# final_1.net
KiCad netlist of a schematic drawn in EAGLE
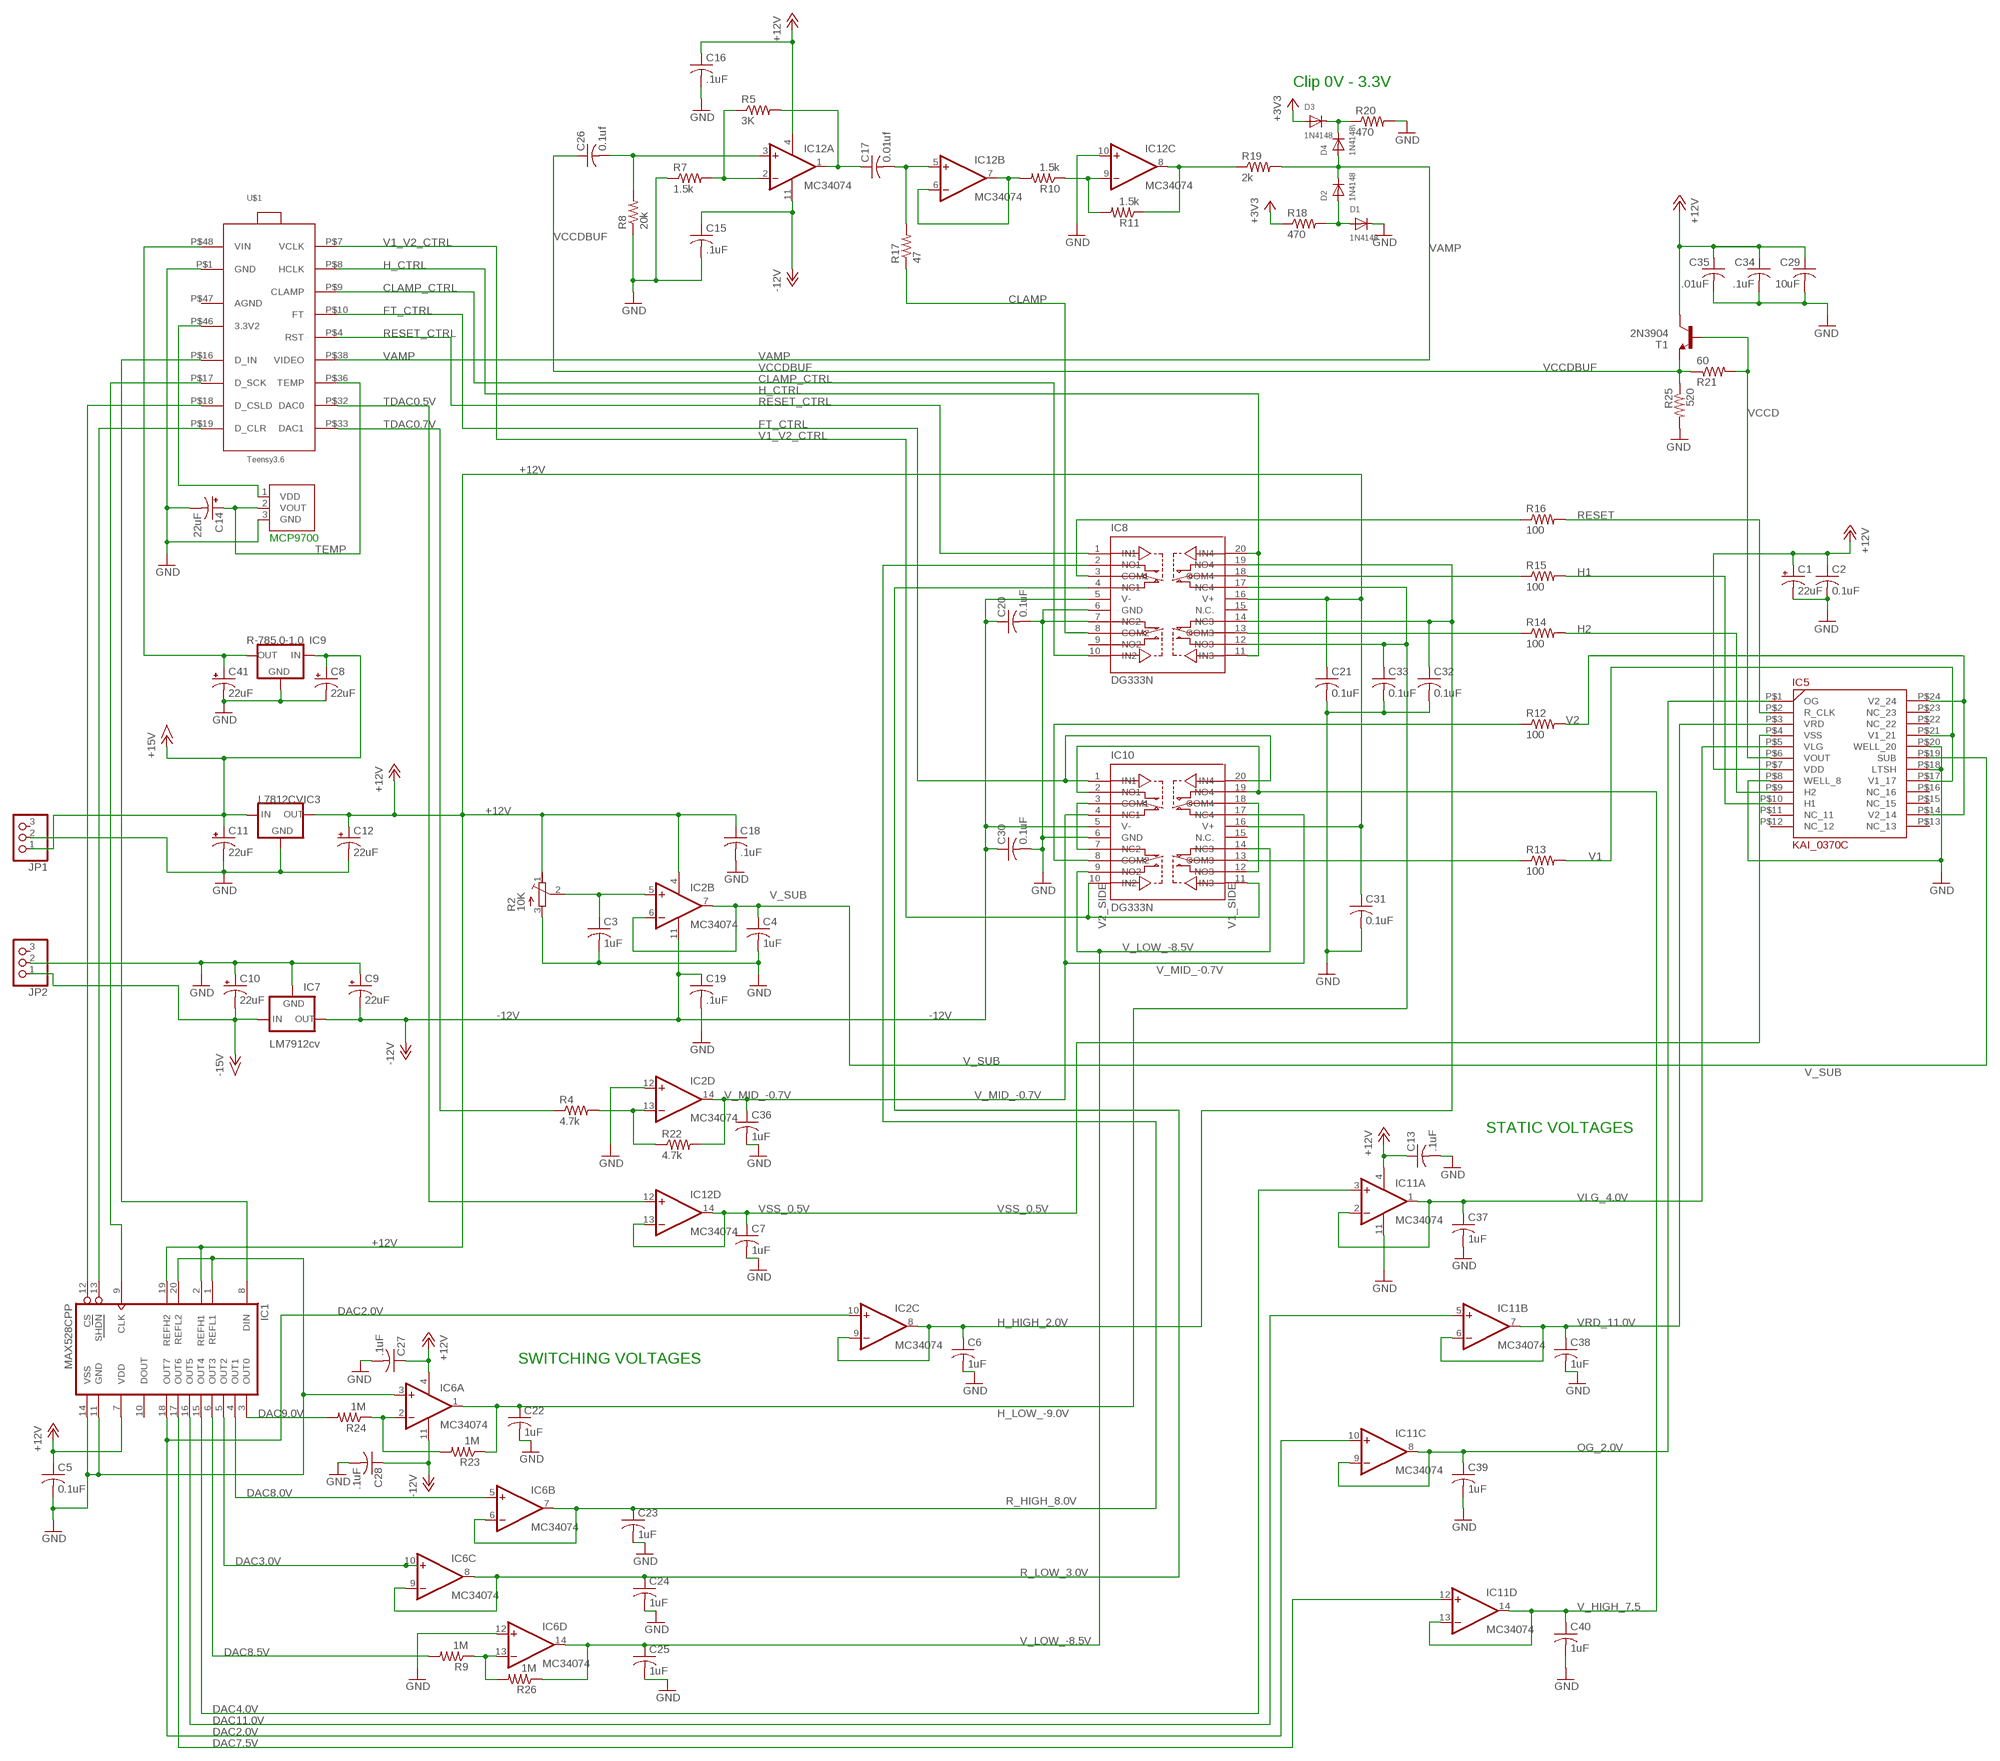
[diagram p0: schematic, sheet 1]

(export (version "E")
  (design (tool "Eeschema 10.0.6"))
  (components
    (comp (ref "C1")
      (value "22uF")
      (footprint "eagle-import:SANYO-OSCON_F")
      (libsource (lib "eagle-import") (part "CPOL-USSANYO_F"))
    )
    (comp (ref "C2")
      (value "0.1uF")
      (footprint "eagle-import:C050-050X075")
      (libsource (lib "eagle-import") (part "C-US050-050X075"))
    )
    (comp (ref "C3")
      (value "1uF")
      (footprint "eagle-import:C050-050X075")
      (libsource (lib "eagle-import") (part "C-US050-050X075"))
    )
    (comp (ref "C4")
      (value "1uF")
      (footprint "eagle-import:C050-050X075")
      (libsource (lib "eagle-import") (part "C-US050-050X075"))
    )
    (comp (ref "C5")
      (value "0.1uF")
      (footprint "eagle-import:C050-050X075")
      (libsource (lib "eagle-import") (part "C-US050-050X075"))
    )
    (comp (ref "C6")
      (value "1uF")
      (footprint "eagle-import:C050-050X075")
      (libsource (lib "eagle-import") (part "C-US050-050X075"))
    )
    (comp (ref "C7")
      (value "1uF")
      (footprint "eagle-import:C050-050X075")
      (libsource (lib "eagle-import") (part "C-US050-050X075"))
    )
    (comp (ref "C8")
      (value "22uF")
      (footprint "eagle-import:SANYO-OSCON_F")
      (libsource (lib "eagle-import") (part "CPOL-USSANYO_F"))
    )
    (comp (ref "C9")
      (value "22uF")
      (footprint "eagle-import:SANYO-OSCON_F")
      (libsource (lib "eagle-import") (part "CPOL-USSANYO_F"))
    )
    (comp (ref "C10")
      (value "22uF")
      (footprint "eagle-import:SANYO-OSCON_F")
      (libsource (lib "eagle-import") (part "CPOL-USSANYO_F"))
    )
    (comp (ref "C11")
      (value "22uF")
      (footprint "eagle-import:SANYO-OSCON_F")
      (libsource (lib "eagle-import") (part "CPOL-USSANYO_F"))
    )
    (comp (ref "C12")
      (value "22uF")
      (footprint "eagle-import:SANYO-OSCON_F")
      (libsource (lib "eagle-import") (part "CPOL-USSANYO_F"))
    )
    (comp (ref "C13")
      (value ".1uF")
      (footprint "eagle-import:C050-050X075")
      (libsource (lib "eagle-import") (part "C-US050-050X075"))
    )
    (comp (ref "C14")
      (value "22uF")
      (footprint "eagle-import:SANYO-OSCON_F")
      (libsource (lib "eagle-import") (part "CPOL-USSANYO_F"))
    )
    (comp (ref "C15")
      (value ".1uF")
      (footprint "eagle-import:C050-050X075")
      (libsource (lib "eagle-import") (part "C-US050-050X075"))
    )
    (comp (ref "C16")
      (value ".1uF")
      (footprint "eagle-import:C050-050X075")
      (libsource (lib "eagle-import") (part "C-US050-050X075"))
    )
    (comp (ref "C17")
      (value "0.01uf")
      (footprint "eagle-import:C050-050X075")
      (libsource (lib "eagle-import") (part "C-US050-050X075"))
    )
    (comp (ref "C18")
      (value ".1uF")
      (footprint "eagle-import:C050-050X075")
      (libsource (lib "eagle-import") (part "C-US050-050X075"))
    )
    (comp (ref "C19")
      (value ".1uF")
      (footprint "eagle-import:C050-050X075")
      (libsource (lib "eagle-import") (part "C-US050-050X075"))
    )
    (comp (ref "C20")
      (value "0.1uF")
      (footprint "eagle-import:C050-050X075")
      (libsource (lib "eagle-import") (part "C-US050-050X075"))
    )
    (comp (ref "C21")
      (value "0.1uF")
      (footprint "eagle-import:C050-050X075")
      (libsource (lib "eagle-import") (part "C-US050-050X075"))
    )
    (comp (ref "C22")
      (value "1uF")
      (footprint "eagle-import:C050-050X075")
      (libsource (lib "eagle-import") (part "C-US050-050X075"))
    )
    (comp (ref "C23")
      (value "1uF")
      (footprint "eagle-import:C050-050X075")
      (libsource (lib "eagle-import") (part "C-US050-050X075"))
    )
    (comp (ref "C24")
      (value "1uF")
      (footprint "eagle-import:C050-050X075")
      (libsource (lib "eagle-import") (part "C-US050-050X075"))
    )
    (comp (ref "C25")
      (value "1uF")
      (footprint "eagle-import:C050-050X075")
      (libsource (lib "eagle-import") (part "C-US050-050X075"))
    )
    (comp (ref "C26")
      (value "0.1uf")
      (footprint "eagle-import:C050-050X075")
      (libsource (lib "eagle-import") (part "C-US050-050X075"))
    )
    (comp (ref "C27")
      (value ".1uF")
      (footprint "eagle-import:C050-050X075")
      (libsource (lib "eagle-import") (part "C-US050-050X075"))
    )
    (comp (ref "C28")
      (value ".1uF")
      (footprint "eagle-import:C050-050X075")
      (libsource (lib "eagle-import") (part "C-US050-050X075"))
    )
    (comp (ref "C29")
      (value "10uF")
      (footprint "eagle-import:C050-050X075")
      (libsource (lib "eagle-import") (part "C-US050-050X075"))
    )
    (comp (ref "C30")
      (value "0.1uF")
      (footprint "eagle-import:C050-050X075")
      (libsource (lib "eagle-import") (part "C-US050-050X075"))
    )
    (comp (ref "C31")
      (value "0.1uF")
      (footprint "eagle-import:C050-050X075")
      (libsource (lib "eagle-import") (part "C-US050-050X075"))
    )
    (comp (ref "C32")
      (value "0.1uF")
      (footprint "eagle-import:C050-050X075")
      (libsource (lib "eagle-import") (part "C-US050-050X075"))
    )
    (comp (ref "C33")
      (value "0.1uF")
      (footprint "eagle-import:C050-050X075")
      (libsource (lib "eagle-import") (part "C-US050-050X075"))
    )
    (comp (ref "C34")
      (value ".1uF")
      (footprint "eagle-import:C050-050X075")
      (libsource (lib "eagle-import") (part "C-US050-050X075"))
    )
    (comp (ref "C35")
      (value ".01uF")
      (footprint "eagle-import:C050-050X075")
      (libsource (lib "eagle-import") (part "C-US050-050X075"))
    )
    (comp (ref "C36")
      (value "1uF")
      (footprint "eagle-import:C050-050X075")
      (libsource (lib "eagle-import") (part "C-US050-050X075"))
    )
    (comp (ref "C37")
      (value "1uF")
      (footprint "eagle-import:C050-050X075")
      (libsource (lib "eagle-import") (part "C-US050-050X075"))
    )
    (comp (ref "C38")
      (value "1uF")
      (footprint "eagle-import:C050-050X075")
      (libsource (lib "eagle-import") (part "C-US050-050X075"))
    )
    (comp (ref "C39")
      (value "1uF")
      (footprint "eagle-import:C050-050X075")
      (libsource (lib "eagle-import") (part "C-US050-050X075"))
    )
    (comp (ref "C40")
      (value "1uF")
      (footprint "eagle-import:C050-050X075")
      (libsource (lib "eagle-import") (part "C-US050-050X075"))
    )
    (comp (ref "C41")
      (value "22uF")
      (footprint "eagle-import:SANYO-OSCON_F")
      (libsource (lib "eagle-import") (part "CPOL-USSANYO_F"))
    )
    (comp (ref "D1")
      (value "1N4148")
      (footprint "eagle-import:DO-1N4148")
      (libsource (lib "eagle-import") (part "DIODEDO-1N4148"))
    )
    (comp (ref "D2")
      (value "1N4148")
      (footprint "eagle-import:DO-1N4148")
      (libsource (lib "eagle-import") (part "DIODEDO-1N4148"))
    )
    (comp (ref "D3")
      (value "1N4148")
      (footprint "eagle-import:DO-1N4148")
      (libsource (lib "eagle-import") (part "DIODEDO-1N4148"))
    )
    (comp (ref "D4")
      (value "1N4148\\")
      (footprint "eagle-import:DO-1N4148")
      (libsource (lib "eagle-import") (part "DIODEDO-1N4148"))
    )
    (comp (ref "IC1")
      (value "MAX528CPP")
      (footprint "eagle-import:DIL20")
      (libsource (lib "eagle-import") (part "MAX528CPP"))
    )
    (comp (ref "IC2")
      (value "MC34074")
      (footprint "eagle-import:DIL14")
      (libsource (lib "eagle-import") (part "LM324N"))
    )
    (comp (ref "IC3")
      (value "L7812CV")
      (footprint "eagle-import:78XXS")
      (libsource (lib "eagle-import") (part "78XXS"))
    )
    (comp (ref "IC5")
      (value "KAI_0370C")
      (footprint "eagle-import:KAI-0370C")
      (libsource (lib "eagle-import") (part "KAI_0370C"))
    )
    (comp (ref "IC6")
      (value "MC34074")
      (footprint "eagle-import:DIL14")
      (libsource (lib "eagle-import") (part "LM324N"))
    )
    (comp (ref "IC7")
      (value "LM7912cv")
      (footprint "eagle-import:79XXS")
      (libsource (lib "eagle-import") (part "79XXS"))
    )
    (comp (ref "IC8")
      (value "DG333N")
      (footprint "eagle-import:DIL20")
      (libsource (lib "eagle-import") (part "MAX333N"))
    )
    (comp (ref "IC9")
      (value "R-785.0-1.0")
      (footprint "eagle-import:SIP3")
      (fields (field (name "MF") "Recom"))
      (libsource (lib "eagle-import") (part "R-78-1.05.0"))
    )
    (comp (ref "IC10")
      (value "DG333N")
      (footprint "eagle-import:DIL20")
      (libsource (lib "eagle-import") (part "MAX333N"))
    )
    (comp (ref "IC11")
      (value "MC34074")
      (footprint "eagle-import:DIL14")
      (libsource (lib "eagle-import") (part "LM324N"))
    )
    (comp (ref "IC12")
      (value "MC34074")
      (footprint "eagle-import:DIL14")
      (libsource (lib "eagle-import") (part "LM324N"))
    )
    (comp (ref "JP1")
      (value "PINHD-1X3")
      (footprint "eagle-import:1X03")
      (libsource (lib "eagle-import") (part "PINHD-1X3"))
    )
    (comp (ref "JP2")
      (value "PINHD-1X3")
      (footprint "eagle-import:1X03")
      (libsource (lib "eagle-import") (part "PINHD-1X3"))
    )
    (comp (ref "R2")
      (value "10K")
      (footprint "eagle-import:RTRIM3006P")
      (libsource (lib "eagle-import") (part "R-TRIMM3006P"))
    )
    (comp (ref "R4")
      (value "4.7k")
      (footprint "eagle-import:0207_2V")
      (libsource (lib "eagle-import") (part "R-US_0207/2V"))
    )
    (comp (ref "R5")
      (value "3K")
      (footprint "eagle-import:0207_2V")
      (libsource (lib "eagle-import") (part "R-US_0207/2V"))
    )
    (comp (ref "R7")
      (value "1.5k")
      (footprint "eagle-import:0207_2V")
      (libsource (lib "eagle-import") (part "R-US_0207/2V"))
    )
    (comp (ref "R8")
      (value "20k")
      (footprint "eagle-import:0207_2V")
      (libsource (lib "eagle-import") (part "R-US_0207/2V"))
    )
    (comp (ref "R9")
      (value "1M")
      (footprint "eagle-import:0207_2V")
      (libsource (lib "eagle-import") (part "R-US_0207/2V"))
    )
    (comp (ref "R10")
      (value "1.5k")
      (footprint "eagle-import:0207_2V")
      (libsource (lib "eagle-import") (part "R-US_0207/2V"))
    )
    (comp (ref "R11")
      (value "1.5k")
      (footprint "eagle-import:0207_2V")
      (libsource (lib "eagle-import") (part "R-US_0207/2V"))
    )
    (comp (ref "R12")
      (value "100")
      (footprint "eagle-import:0207_2V")
      (libsource (lib "eagle-import") (part "R-US_0207/2V"))
    )
    (comp (ref "R13")
      (value "100")
      (footprint "eagle-import:0207_2V")
      (libsource (lib "eagle-import") (part "R-US_0207/2V"))
    )
    (comp (ref "R14")
      (value "100")
      (footprint "eagle-import:0207_2V")
      (libsource (lib "eagle-import") (part "R-US_0207/2V"))
    )
    (comp (ref "R15")
      (value "100")
      (footprint "eagle-import:0207_2V")
      (libsource (lib "eagle-import") (part "R-US_0207/2V"))
    )
    (comp (ref "R16")
      (value "100")
      (footprint "eagle-import:0207_2V")
      (libsource (lib "eagle-import") (part "R-US_0207/2V"))
    )
    (comp (ref "R17")
      (value "47")
      (footprint "eagle-import:0207_2V")
      (libsource (lib "eagle-import") (part "R-US_0207/2V"))
    )
    (comp (ref "R18")
      (value "470")
      (footprint "eagle-import:0207_2V")
      (libsource (lib "eagle-import") (part "R-US_0207/2V"))
    )
    (comp (ref "R19")
      (value "2k")
      (footprint "eagle-import:0207_2V")
      (libsource (lib "eagle-import") (part "R-US_0207/2V"))
    )
    (comp (ref "R20")
      (value "470")
      (footprint "eagle-import:0207_2V")
      (libsource (lib "eagle-import") (part "R-US_0207/2V"))
    )
    (comp (ref "R21")
      (value "60")
      (footprint "eagle-import:0207_2V")
      (libsource (lib "eagle-import") (part "R-US_0207/2V"))
    )
    (comp (ref "R22")
      (value "4.7k")
      (footprint "eagle-import:0207_2V")
      (libsource (lib "eagle-import") (part "R-US_0207/2V"))
    )
    (comp (ref "R23")
      (value "1M")
      (footprint "eagle-import:0207_2V")
      (libsource (lib "eagle-import") (part "R-US_0207/2V"))
    )
    (comp (ref "R24")
      (value "1M")
      (footprint "eagle-import:0207_2V")
      (libsource (lib "eagle-import") (part "R-US_0207/2V"))
    )
    (comp (ref "R25")
      (value "520")
      (footprint "eagle-import:0207_2V")
      (libsource (lib "eagle-import") (part "R-US_0207/2V"))
    )
    (comp (ref "R26")
      (value "1M")
      (footprint "eagle-import:0207_2V")
      (libsource (lib "eagle-import") (part "R-US_0207/2V"))
    )
    (comp (ref "T1")
      (value "2N3904")
      (footprint "eagle-import:TO92")
      (libsource (lib "eagle-import") (part "2N3904"))
    )
    (comp (ref "U$1")
      (value "TEENSY3.6LIMITED")
      (footprint "eagle-import:DIL")
      (libsource (lib "eagle-import") (part "TEENSY3.6LIMITED"))
    )
    (comp (ref "U$2")
      (value "MCP970XTO")
      (footprint "eagle-import:TO92")
      (libsource (lib "eagle-import") (part "MCP970XTO"))
    )
  )
  (nets
    (net (code "1") (name "+3V3") (class "Default")
      (node (ref "D3") (pin "A") (pinfunction "A_A") (pintype "passive"))
      (node (ref "R18") (pin "1") (pinfunction "1_1") (pintype "passive"))
    )
    (net (code "2") (name "+12V") (class "Default")
      (node (ref "C1") (pin "+") (pinfunction "+_+") (pintype "passive"))
      (node (ref "C12") (pin "+") (pinfunction "+_+") (pintype "passive"))
      (node (ref "C13") (pin "1") (pinfunction "1_1") (pintype "passive"))
      (node (ref "C16") (pin "1") (pinfunction "1_1") (pintype "passive"))
      (node (ref "C18") (pin "1") (pinfunction "1_1") (pintype "passive"))
      (node (ref "C2") (pin "1") (pinfunction "1_1") (pintype "passive"))
      (node (ref "C21") (pin "1") (pinfunction "1_1") (pintype "passive"))
      (node (ref "C27") (pin "1") (pinfunction "1_1") (pintype "passive"))
      (node (ref "C29") (pin "1") (pinfunction "1_1") (pintype "passive"))
      (node (ref "C31") (pin "1") (pinfunction "1_1") (pintype "passive"))
      (node (ref "C34") (pin "1") (pinfunction "1_1") (pintype "passive"))
      (node (ref "C35") (pin "1") (pinfunction "1_1") (pintype "passive"))
      (node (ref "C5") (pin "1") (pinfunction "1_1") (pintype "passive"))
      (node (ref "IC1") (pin "19") (pinfunction "REFH2_19") (pintype "input"))
      (node (ref "IC1") (pin "2") (pinfunction "REFH1_2") (pintype "input"))
      (node (ref "IC1") (pin "7") (pinfunction "VDD_7") (pintype "power_in"))
      (node (ref "IC10") (pin "16") (pinfunction "V+_16") (pintype "passive"))
      (node (ref "IC11") (pin "4") (pinfunction "V+_4") (pintype "power_in"))
      (node (ref "IC12") (pin "4") (pinfunction "V+_4") (pintype "power_in"))
      (node (ref "IC2") (pin "4") (pinfunction "V+_4") (pintype "power_in"))
      (node (ref "IC3") (pin "OUT") (pinfunction "OUT_OUT") (pintype "passive"))
      (node (ref "IC5") (pin "P$7") (pinfunction "VDD_P$7") (pintype "passive"))
      (node (ref "IC6") (pin "4") (pinfunction "V+_4") (pintype "power_in"))
      (node (ref "IC8") (pin "16") (pinfunction "V+_16") (pintype "passive"))
      (node (ref "R2") (pin "1") (pinfunction "A_1") (pintype "passive"))
      (node (ref "T1") (pin "1") (pinfunction "C_1") (pintype "passive"))
    )
    (net (code "3") (name "+15V") (class "Default")
      (node (ref "C11") (pin "+") (pinfunction "+_+") (pintype "passive"))
      (node (ref "C8") (pin "+") (pinfunction "+_+") (pintype "passive"))
      (node (ref "IC3") (pin "IN") (pinfunction "IN_IN") (pintype "input"))
      (node (ref "IC9") (pin "1") (pinfunction "IN_1") (pintype "input"))
      (node (ref "JP1") (pin "1") (pinfunction "1_1") (pintype "passive"))
    )
    (net (code "4") (name "-12V") (class "Default")
      (node (ref "C15") (pin "1") (pinfunction "1_1") (pintype "passive"))
      (node (ref "C19") (pin "1") (pinfunction "1_1") (pintype "passive"))
      (node (ref "C20") (pin "1") (pinfunction "1_1") (pintype "passive"))
      (node (ref "C28") (pin "1") (pinfunction "1_1") (pintype "passive"))
      (node (ref "C30") (pin "1") (pinfunction "1_1") (pintype "passive"))
      (node (ref "C9") (pin "-") (pinfunction "-_-") (pintype "passive"))
      (node (ref "IC10") (pin "5") (pinfunction "V-_5") (pintype "passive"))
      (node (ref "IC12") (pin "11") (pinfunction "V-_11") (pintype "power_in"))
      (node (ref "IC2") (pin "11") (pinfunction "V-_11") (pintype "power_in"))
      (node (ref "IC6") (pin "11") (pinfunction "V-_11") (pintype "power_in"))
      (node (ref "IC7") (pin "OUT") (pinfunction "OUT_OUT") (pintype "passive"))
      (node (ref "IC8") (pin "5") (pinfunction "V-_5") (pintype "passive"))
    )
    (net (code "5") (name "-15V") (class "Default")
      (node (ref "C10") (pin "-") (pinfunction "-_-") (pintype "passive"))
      (node (ref "IC7") (pin "IN") (pinfunction "IN_IN") (pintype "input"))
      (node (ref "JP2") (pin "1") (pinfunction "1_1") (pintype "passive"))
    )
    (net (code "6") (name "/AGND") (class "Default")
      (node (ref "U$1") (pin "P$47") (pinfunction "AGND_P$47") (pintype "power_in"))
    )
    (net (code "7") (name "/CLAMP") (class "Default")
      (node (ref "IC8") (pin "8") (pinfunction "COM2_8") (pintype "passive"))
      (node (ref "R17") (pin "1") (pinfunction "1_1") (pintype "passive"))
    )
    (net (code "8") (name "/CLAMP_CTRL") (class "Default")
      (node (ref "IC8") (pin "10") (pinfunction "IN2_10") (pintype "passive"))
      (node (ref "U$1") (pin "P$9") (pinfunction "CLAMP_P$9") (pintype "output"))
    )
    (net (code "9") (name "/DAC2.0V") (class "Default")
      (node (ref "IC1") (pin "18") (pinfunction "OUT7_18") (pintype "output"))
      (node (ref "IC11") (pin "10") (pinfunction "+IN_10") (pintype "input"))
      (node (ref "IC2") (pin "10") (pinfunction "+IN_10") (pintype "input"))
    )
    (net (code "10") (name "/DAC3.0V") (class "Default")
      (node (ref "IC1") (pin "5") (pinfunction "OUT2_5") (pintype "output"))
      (node (ref "IC6") (pin "10") (pinfunction "+IN_10") (pintype "input"))
    )
    (net (code "11") (name "/DAC4.0V") (class "Default")
      (node (ref "IC1") (pin "15") (pinfunction "OUT4_15") (pintype "output"))
      (node (ref "IC11") (pin "3") (pinfunction "+IN_3") (pintype "input"))
    )
    (net (code "12") (name "/DAC7.5V") (class "Default")
      (node (ref "IC1") (pin "17") (pinfunction "OUT6_17") (pintype "output"))
      (node (ref "IC11") (pin "12") (pinfunction "+IN_12") (pintype "input"))
    )
    (net (code "13") (name "/DAC8.0V") (class "Default")
      (node (ref "IC1") (pin "4") (pinfunction "OUT1_4") (pintype "output"))
      (node (ref "IC6") (pin "5") (pinfunction "+IN_5") (pintype "input"))
    )
    (net (code "14") (name "/DAC8.5V") (class "Default")
      (node (ref "IC1") (pin "6") (pinfunction "OUT3_6") (pintype "output"))
      (node (ref "R9") (pin "2") (pinfunction "2_2") (pintype "passive"))
    )
    (net (code "15") (name "/DAC9.0V") (class "Default")
      (node (ref "IC1") (pin "3") (pinfunction "OUT0_3") (pintype "output"))
      (node (ref "R24") (pin "2") (pinfunction "2_2") (pintype "passive"))
    )
    (net (code "16") (name "/DAC11.0V") (class "Default")
      (node (ref "IC1") (pin "16") (pinfunction "OUT5_16") (pintype "output"))
      (node (ref "IC11") (pin "5") (pinfunction "+IN_5") (pintype "input"))
    )
    (net (code "17") (name "/FT_CTRL") (class "Default")
      (node (ref "IC10") (pin "1") (pinfunction "IN1_1") (pintype "passive"))
      (node (ref "IC10") (pin "20") (pinfunction "IN4_20") (pintype "passive"))
      (node (ref "U$1") (pin "P$10") (pinfunction "FT_P$10") (pintype "output"))
    )
    (net (code "18") (name "/H1") (class "Default")
      (node (ref "IC5") (pin "P$10") (pinfunction "H1_P$10") (pintype "passive"))
      (node (ref "R15") (pin "2") (pinfunction "2_2") (pintype "passive"))
    )
    (net (code "19") (name "/H2") (class "Default")
      (node (ref "IC5") (pin "P$9") (pinfunction "H2_P$9") (pintype "passive"))
      (node (ref "R14") (pin "2") (pinfunction "2_2") (pintype "passive"))
    )
    (net (code "20") (name "/H_CTRL") (class "Default")
      (node (ref "IC8") (pin "11") (pinfunction "IN3_11") (pintype "passive"))
      (node (ref "IC8") (pin "20") (pinfunction "IN4_20") (pintype "passive"))
      (node (ref "U$1") (pin "P$8") (pinfunction "HCLK_P$8") (pintype "output"))
    )
    (net (code "21") (name "/H_HIGH_2.0V") (class "Default")
      (node (ref "C32") (pin "1") (pinfunction "1_1") (pintype "passive"))
      (node (ref "C6") (pin "1") (pinfunction "1_1") (pintype "passive"))
      (node (ref "IC2") (pin "8") (pinfunction "OUT_8") (pintype "output"))
      (node (ref "IC2") (pin "9") (pinfunction "-IN_9") (pintype "input"))
      (node (ref "IC8") (pin "14") (pinfunction "NC3_14") (pintype "passive"))
      (node (ref "IC8") (pin "19") (pinfunction "NO4_19") (pintype "passive"))
    )
    (net (code "22") (name "/H_LOW_-9.0V") (class "Default")
      (node (ref "C22") (pin "1") (pinfunction "1_1") (pintype "passive"))
      (node (ref "C33") (pin "1") (pinfunction "1_1") (pintype "passive"))
      (node (ref "IC6") (pin "1") (pinfunction "OUT_1") (pintype "output"))
      (node (ref "IC8") (pin "12") (pinfunction "NO3_12") (pintype "passive"))
      (node (ref "IC8") (pin "17") (pinfunction "NC4_17") (pintype "passive"))
      (node (ref "R23") (pin "1") (pinfunction "1_1") (pintype "passive"))
    )
    (net (code "23") (name "/OG_2.0V") (class "Default")
      (node (ref "C39") (pin "1") (pinfunction "1_1") (pintype "passive"))
      (node (ref "IC11") (pin "8") (pinfunction "OUT_8") (pintype "output"))
      (node (ref "IC11") (pin "9") (pinfunction "-IN_9") (pintype "input"))
      (node (ref "IC5") (pin "P$1") (pinfunction "OG_P$1") (pintype "passive"))
    )
    (net (code "24") (name "/RESET") (class "Default")
      (node (ref "IC8") (pin "3") (pinfunction "COM1_3") (pintype "passive"))
      (node (ref "R16") (pin "1") (pinfunction "1_1") (pintype "passive"))
    )
    (net (code "25") (name "/RESET_CTRL") (class "Default")
      (node (ref "IC8") (pin "1") (pinfunction "IN1_1") (pintype "passive"))
      (node (ref "U$1") (pin "P$4") (pinfunction "RST_P$4") (pintype "output"))
    )
    (net (code "26") (name "/R_HIGH_8.0V") (class "Default")
      (node (ref "C23") (pin "1") (pinfunction "1_1") (pintype "passive"))
      (node (ref "IC6") (pin "6") (pinfunction "-IN_6") (pintype "input"))
      (node (ref "IC6") (pin "7") (pinfunction "OUT_7") (pintype "output"))
      (node (ref "IC8") (pin "2") (pinfunction "NO1_2") (pintype "passive"))
    )
    (net (code "27") (name "/R_LOW_3.0V") (class "Default")
      (node (ref "C24") (pin "1") (pinfunction "1_1") (pintype "passive"))
      (node (ref "IC6") (pin "8") (pinfunction "OUT_8") (pintype "output"))
      (node (ref "IC6") (pin "9") (pinfunction "-IN_9") (pintype "input"))
      (node (ref "IC8") (pin "4") (pinfunction "NC1_4") (pintype "passive"))
    )
    (net (code "28") (name "/TDAC0.5V") (class "Default")
      (node (ref "IC12") (pin "12") (pinfunction "+IN_12") (pintype "input"))
      (node (ref "U$1") (pin "P$32") (pinfunction "DAC0_P$32") (pintype "output"))
    )
    (net (code "29") (name "/TDAC0.7V") (class "Default")
      (node (ref "R4") (pin "1") (pinfunction "1_1") (pintype "passive"))
      (node (ref "U$1") (pin "P$33") (pinfunction "DAC1_P$33") (pintype "output"))
    )
    (net (code "30") (name "/TEMP") (class "Default")
      (node (ref "C14") (pin "+") (pinfunction "+_+") (pintype "passive"))
      (node (ref "U$1") (pin "P$36") (pinfunction "TEMP_P$36") (pintype "input"))
      (node (ref "U$2") (pin "2") (pinfunction "VOUT_2") (pintype "output"))
    )
    (net (code "31") (name "/V1") (class "Default")
      (node (ref "IC5") (pin "P$17") (pinfunction "V1_17_P$17") (pintype "passive"))
      (node (ref "IC5") (pin "P$21") (pinfunction "V1_21_P$21") (pintype "passive"))
      (node (ref "R13") (pin "2") (pinfunction "2_2") (pintype "passive"))
    )
    (net (code "32") (name "/V1_V2_CTRL") (class "Default")
      (node (ref "IC10") (pin "10") (pinfunction "IN2_10") (pintype "passive"))
      (node (ref "IC10") (pin "11") (pinfunction "IN3_11") (pintype "passive"))
      (node (ref "U$1") (pin "P$7") (pinfunction "VCLK_P$7") (pintype "output"))
    )
    (net (code "33") (name "/V2") (class "Default")
      (node (ref "IC5") (pin "P$14") (pinfunction "V2_14_P$14") (pintype "passive"))
      (node (ref "IC5") (pin "P$24") (pinfunction "V2_24_P$24") (pintype "passive"))
      (node (ref "R12") (pin "2") (pinfunction "2_2") (pintype "passive"))
    )
    (net (code "34") (name "/VAMP") (class "Default")
      (node (ref "D2") (pin "C") (pinfunction "C_C") (pintype "passive"))
      (node (ref "D4") (pin "A") (pinfunction "A_A") (pintype "passive"))
      (node (ref "R19") (pin "2") (pinfunction "2_2") (pintype "passive"))
      (node (ref "U$1") (pin "P$38") (pinfunction "VIDEO_P$38") (pintype "input"))
    )
    (net (code "35") (name "/VCCD") (class "Default")
      (node (ref "IC5") (pin "P$6") (pinfunction "VOUT_P$6") (pintype "passive"))
      (node (ref "R21") (pin "2") (pinfunction "2_2") (pintype "passive"))
      (node (ref "T1") (pin "2") (pinfunction "B_2") (pintype "passive"))
    )
    (net (code "36") (name "/VCCDBUF") (class "Default")
      (node (ref "C26") (pin "1") (pinfunction "1_1") (pintype "passive"))
      (node (ref "R21") (pin "1") (pinfunction "1_1") (pintype "passive"))
      (node (ref "R25") (pin "1") (pinfunction "1_1") (pintype "passive"))
      (node (ref "T1") (pin "3") (pinfunction "E_3") (pintype "passive"))
    )
    (net (code "37") (name "/VLG_4.0V") (class "Default")
      (node (ref "C37") (pin "1") (pinfunction "1_1") (pintype "passive"))
      (node (ref "IC11") (pin "1") (pinfunction "OUT_1") (pintype "output"))
      (node (ref "IC11") (pin "2") (pinfunction "-IN_2") (pintype "input"))
      (node (ref "IC5") (pin "P$5") (pinfunction "VLG_P$5") (pintype "passive"))
    )
    (net (code "38") (name "/VRD_11.0V") (class "Default")
      (node (ref "C38") (pin "1") (pinfunction "1_1") (pintype "passive"))
      (node (ref "IC11") (pin "6") (pinfunction "-IN_6") (pintype "input"))
      (node (ref "IC11") (pin "7") (pinfunction "OUT_7") (pintype "output"))
      (node (ref "IC5") (pin "P$3") (pinfunction "VRD_P$3") (pintype "passive"))
    )
    (net (code "39") (name "/VSS_0.5V") (class "Default")
      (node (ref "C7") (pin "1") (pinfunction "1_1") (pintype "passive"))
      (node (ref "IC12") (pin "13") (pinfunction "-IN_13") (pintype "input"))
      (node (ref "IC12") (pin "14") (pinfunction "OUT_14") (pintype "output"))
      (node (ref "IC5") (pin "P$4") (pinfunction "VSS_P$4") (pintype "passive"))
    )
    (net (code "40") (name "/V_HIGH_7.5") (class "Default")
      (node (ref "C40") (pin "1") (pinfunction "1_1") (pintype "passive"))
      (node (ref "IC10") (pin "19") (pinfunction "NO4_19") (pintype "passive"))
      (node (ref "IC10") (pin "2") (pinfunction "NO1_2") (pintype "passive"))
      (node (ref "IC11") (pin "13") (pinfunction "-IN_13") (pintype "input"))
      (node (ref "IC11") (pin "14") (pinfunction "OUT_14") (pintype "output"))
    )
    (net (code "41") (name "/V_LOW_-8.5V") (class "Default")
      (node (ref "C25") (pin "1") (pinfunction "1_1") (pintype "passive"))
      (node (ref "IC10") (pin "14") (pinfunction "NC3_14") (pintype "passive"))
      (node (ref "IC10") (pin "9") (pinfunction "NO2_9") (pintype "passive"))
      (node (ref "IC6") (pin "14") (pinfunction "OUT_14") (pintype "output"))
      (node (ref "R26") (pin "1") (pinfunction "1_1") (pintype "passive"))
    )
    (net (code "42") (name "/V_MID_-0.7V") (class "Default")
      (node (ref "C36") (pin "1") (pinfunction "1_1") (pintype "passive"))
      (node (ref "IC10") (pin "17") (pinfunction "NC4_17") (pintype "passive"))
      (node (ref "IC10") (pin "4") (pinfunction "NC1_4") (pintype "passive"))
      (node (ref "IC2") (pin "14") (pinfunction "OUT_14") (pintype "output"))
      (node (ref "R22") (pin "2") (pinfunction "2_2") (pintype "passive"))
    )
    (net (code "43") (name "/V_SUB") (class "Default")
      (node (ref "C4") (pin "1") (pinfunction "1_1") (pintype "passive"))
      (node (ref "IC2") (pin "6") (pinfunction "-IN_6") (pintype "input"))
      (node (ref "IC2") (pin "7") (pinfunction "OUT_7") (pintype "output"))
      (node (ref "IC5") (pin "P$19") (pinfunction "SUB_P$19") (pintype "passive"))
    )
    (net (code "44") (name "GND") (class "Default")
      (node (ref "C1") (pin "-") (pinfunction "-_-") (pintype "passive"))
      (node (ref "C10") (pin "+") (pinfunction "+_+") (pintype "passive"))
      (node (ref "C11") (pin "-") (pinfunction "-_-") (pintype "passive"))
      (node (ref "C12") (pin "-") (pinfunction "-_-") (pintype "passive"))
      (node (ref "C13") (pin "2") (pinfunction "2_2") (pintype "passive"))
      (node (ref "C14") (pin "-") (pinfunction "-_-") (pintype "passive"))
      (node (ref "C15") (pin "2") (pinfunction "2_2") (pintype "passive"))
      (node (ref "C16") (pin "2") (pinfunction "2_2") (pintype "passive"))
      (node (ref "C18") (pin "2") (pinfunction "2_2") (pintype "passive"))
      (node (ref "C19") (pin "2") (pinfunction "2_2") (pintype "passive"))
      (node (ref "C2") (pin "2") (pinfunction "2_2") (pintype "passive"))
      (node (ref "C20") (pin "2") (pinfunction "2_2") (pintype "passive"))
      (node (ref "C21") (pin "2") (pinfunction "2_2") (pintype "passive"))
      (node (ref "C22") (pin "2") (pinfunction "2_2") (pintype "passive"))
      (node (ref "C23") (pin "2") (pinfunction "2_2") (pintype "passive"))
      (node (ref "C24") (pin "2") (pinfunction "2_2") (pintype "passive"))
      (node (ref "C25") (pin "2") (pinfunction "2_2") (pintype "passive"))
      (node (ref "C27") (pin "2") (pinfunction "2_2") (pintype "passive"))
      (node (ref "C28") (pin "2") (pinfunction "2_2") (pintype "passive"))
      (node (ref "C29") (pin "2") (pinfunction "2_2") (pintype "passive"))
      (node (ref "C3") (pin "2") (pinfunction "2_2") (pintype "passive"))
      (node (ref "C30") (pin "2") (pinfunction "2_2") (pintype "passive"))
      (node (ref "C31") (pin "2") (pinfunction "2_2") (pintype "passive"))
      (node (ref "C32") (pin "2") (pinfunction "2_2") (pintype "passive"))
      (node (ref "C33") (pin "2") (pinfunction "2_2") (pintype "passive"))
      (node (ref "C34") (pin "2") (pinfunction "2_2") (pintype "passive"))
      (node (ref "C35") (pin "2") (pinfunction "2_2") (pintype "passive"))
      (node (ref "C36") (pin "2") (pinfunction "2_2") (pintype "passive"))
      (node (ref "C37") (pin "2") (pinfunction "2_2") (pintype "passive"))
      (node (ref "C38") (pin "2") (pinfunction "2_2") (pintype "passive"))
      (node (ref "C39") (pin "2") (pinfunction "2_2") (pintype "passive"))
      (node (ref "C4") (pin "2") (pinfunction "2_2") (pintype "passive"))
      (node (ref "C40") (pin "2") (pinfunction "2_2") (pintype "passive"))
      (node (ref "C41") (pin "-") (pinfunction "-_-") (pintype "passive"))
      (node (ref "C5") (pin "2") (pinfunction "2_2") (pintype "passive"))
      (node (ref "C6") (pin "2") (pinfunction "2_2") (pintype "passive"))
      (node (ref "C7") (pin "2") (pinfunction "2_2") (pintype "passive"))
      (node (ref "C8") (pin "-") (pinfunction "-_-") (pintype "passive"))
      (node (ref "C9") (pin "+") (pinfunction "+_+") (pintype "passive"))
      (node (ref "D1") (pin "C") (pinfunction "C_C") (pintype "passive"))
      (node (ref "IC1") (pin "1") (pinfunction "REFL1_1") (pintype "input"))
      (node (ref "IC1") (pin "11") (pinfunction "GND_11") (pintype "power_in"))
      (node (ref "IC1") (pin "14") (pinfunction "VSS_14") (pintype "power_in"))
      (node (ref "IC1") (pin "20") (pinfunction "REFL2_20") (pintype "input"))
      (node (ref "IC10") (pin "6") (pinfunction "GND_6") (pintype "passive"))
      (node (ref "IC11") (pin "11") (pinfunction "V-_11") (pintype "power_in"))
      (node (ref "IC12") (pin "10") (pinfunction "+IN_10") (pintype "input"))
      (node (ref "IC2") (pin "12") (pinfunction "+IN_12") (pintype "input"))
      (node (ref "IC3") (pin "GND") (pinfunction "GND_GND") (pintype "input"))
      (node (ref "IC5") (pin "P$18") (pinfunction "LTSH_P$18") (pintype "passive"))
      (node (ref "IC5") (pin "P$20") (pinfunction "WELL_20_P$20") (pintype "passive"))
      (node (ref "IC5") (pin "P$8") (pinfunction "WELL_8_P$8") (pintype "passive"))
      (node (ref "IC6") (pin "12") (pinfunction "+IN_12") (pintype "input"))
      (node (ref "IC6") (pin "3") (pinfunction "+IN_3") (pintype "input"))
      (node (ref "IC7") (pin "GND") (pinfunction "GND_GND") (pintype "input"))
      (node (ref "IC8") (pin "6") (pinfunction "GND_6") (pintype "passive"))
      (node (ref "IC8") (pin "7") (pinfunction "NC2_7") (pintype "passive"))
      (node (ref "IC9") (pin "2") (pinfunction "GND_2") (pintype "input"))
      (node (ref "JP1") (pin "2") (pinfunction "2_2") (pintype "passive"))
      (node (ref "JP2") (pin "2") (pinfunction "2_2") (pintype "passive"))
      (node (ref "R2") (pin "3") (pinfunction "E_3") (pintype "passive"))
      (node (ref "R20") (pin "2") (pinfunction "2_2") (pintype "passive"))
      (node (ref "R25") (pin "2") (pinfunction "2_2") (pintype "passive"))
      (node (ref "R7") (pin "1") (pinfunction "1_1") (pintype "passive"))
      (node (ref "R8") (pin "1") (pinfunction "1_1") (pintype "passive"))
      (node (ref "U$1") (pin "P$1") (pinfunction "GND_P$1") (pintype "power_in"))
      (node (ref "U$2") (pin "3") (pinfunction "GND_3") (pintype "power_in"))
    )
    (net (code "45") (name "Net-(D1-PadA)") (class "Default")
      (node (ref "D1") (pin "A") (pinfunction "A_A") (pintype "passive"))
      (node (ref "D2") (pin "A") (pinfunction "A_A") (pintype "passive"))
      (node (ref "R18") (pin "2") (pinfunction "2_2") (pintype "passive"))
    )
    (net (code "46") (name "Net-(D3-PadC)") (class "Default")
      (node (ref "D3") (pin "C") (pinfunction "C_C") (pintype "passive"))
      (node (ref "D4") (pin "C") (pinfunction "C_C") (pintype "passive"))
      (node (ref "R20") (pin "1") (pinfunction "1_1") (pintype "passive"))
    )
    (net (code "47") (name "Net-(IC1-CLK)") (class "Default")
      (node (ref "IC1") (pin "9") (pinfunction "CLK_9") (pintype "input"))
      (node (ref "U$1") (pin "P$17") (pinfunction "D_SCK_P$17") (pintype "output"))
    )
    (net (code "48") (name "Net-(IC1-CS)") (class "Default")
      (node (ref "IC1") (pin "12") (pinfunction "CS_12") (pintype "input"))
      (node (ref "U$1") (pin "P$18") (pinfunction "D_CSLD_P$18") (pintype "output"))
    )
    (net (code "49") (name "Net-(IC1-DIN)") (class "Default")
      (node (ref "IC1") (pin "8") (pinfunction "DIN_8") (pintype "input"))
      (node (ref "U$1") (pin "P$16") (pinfunction "D_IN_P$16") (pintype "output"))
    )
    (net (code "50") (name "Net-(IC1-SHDN)") (class "Default")
      (node (ref "IC1") (pin "13") (pinfunction "SHDN_13") (pintype "input"))
      (node (ref "U$1") (pin "P$19") (pinfunction "D_CLR_P$19") (pintype "output"))
    )
    (net (code "51") (name "Net-(IC2B-+IN)") (class "Default")
      (node (ref "C3") (pin "1") (pinfunction "1_1") (pintype "passive"))
      (node (ref "IC2") (pin "5") (pinfunction "+IN_5") (pintype "input"))
      (node (ref "R2") (pin "2") (pinfunction "S_2") (pintype "passive"))
    )
    (net (code "52") (name "Net-(IC2D--IN)") (class "Default")
      (node (ref "IC2") (pin "13") (pinfunction "-IN_13") (pintype "input"))
      (node (ref "R22") (pin "1") (pinfunction "1_1") (pintype "passive"))
      (node (ref "R4") (pin "2") (pinfunction "2_2") (pintype "passive"))
    )
    (net (code "53") (name "Net-(IC5-R_CLK)") (class "Default")
      (node (ref "IC5") (pin "P$2") (pinfunction "R_CLK_P$2") (pintype "passive"))
      (node (ref "R16") (pin "2") (pinfunction "2_2") (pintype "passive"))
    )
    (net (code "54") (name "Net-(IC6A--IN)") (class "Default")
      (node (ref "IC6") (pin "2") (pinfunction "-IN_2") (pintype "input"))
      (node (ref "R23") (pin "2") (pinfunction "2_2") (pintype "passive"))
      (node (ref "R24") (pin "1") (pinfunction "1_1") (pintype "passive"))
    )
    (net (code "55") (name "Net-(IC6D--IN)") (class "Default")
      (node (ref "IC6") (pin "13") (pinfunction "-IN_13") (pintype "input"))
      (node (ref "R26") (pin "2") (pinfunction "2_2") (pintype "passive"))
      (node (ref "R9") (pin "1") (pinfunction "1_1") (pintype "passive"))
    )
    (net (code "56") (name "Net-(IC8-COM3)") (class "Default")
      (node (ref "IC8") (pin "13") (pinfunction "COM3_13") (pintype "passive"))
      (node (ref "R14") (pin "1") (pinfunction "1_1") (pintype "passive"))
    )
    (net (code "57") (name "Net-(IC8-COM4)") (class "Default")
      (node (ref "IC8") (pin "18") (pinfunction "COM4_18") (pintype "passive"))
      (node (ref "R15") (pin "1") (pinfunction "1_1") (pintype "passive"))
    )
    (net (code "58") (name "Net-(IC9-OUT)") (class "Default")
      (node (ref "C41") (pin "+") (pinfunction "+_+") (pintype "passive"))
      (node (ref "IC9") (pin "3") (pinfunction "OUT_3") (pintype "passive"))
      (node (ref "U$1") (pin "P$48") (pinfunction "VIN_P$48") (pintype "power_in"))
    )
    (net (code "59") (name "Net-(IC10-COM1)") (class "Default")
      (node (ref "IC10") (pin "3") (pinfunction "COM1_3") (pintype "passive"))
      (node (ref "IC10") (pin "7") (pinfunction "NC2_7") (pintype "passive"))
    )
    (net (code "60") (name "Net-(IC10-COM2)") (class "Default")
      (node (ref "IC10") (pin "8") (pinfunction "COM2_8") (pintype "passive"))
      (node (ref "R12") (pin "1") (pinfunction "1_1") (pintype "passive"))
    )
    (net (code "61") (name "Net-(IC10-COM3)") (class "Default")
      (node (ref "IC10") (pin "13") (pinfunction "COM3_13") (pintype "passive"))
      (node (ref "R13") (pin "1") (pinfunction "1_1") (pintype "passive"))
    )
    (net (code "62") (name "Net-(IC10-COM4)") (class "Default")
      (node (ref "IC10") (pin "12") (pinfunction "NO3_12") (pintype "passive"))
      (node (ref "IC10") (pin "18") (pinfunction "COM4_18") (pintype "passive"))
    )
    (net (code "63") (name "Net-(IC12A-+IN)") (class "Default")
      (node (ref "C26") (pin "2") (pinfunction "2_2") (pintype "passive"))
      (node (ref "IC12") (pin "3") (pinfunction "+IN_3") (pintype "input"))
      (node (ref "R8") (pin "2") (pinfunction "2_2") (pintype "passive"))
    )
    (net (code "64") (name "Net-(IC12A--IN)") (class "Default")
      (node (ref "IC12") (pin "2") (pinfunction "-IN_2") (pintype "input"))
      (node (ref "R5") (pin "1") (pinfunction "1_1") (pintype "passive"))
      (node (ref "R7") (pin "2") (pinfunction "2_2") (pintype "passive"))
    )
    (net (code "65") (name "Net-(IC12A-OUT)") (class "Default")
      (node (ref "C17") (pin "1") (pinfunction "1_1") (pintype "passive"))
      (node (ref "IC12") (pin "1") (pinfunction "OUT_1") (pintype "output"))
      (node (ref "R5") (pin "2") (pinfunction "2_2") (pintype "passive"))
    )
    (net (code "66") (name "Net-(IC12B-+IN)") (class "Default")
      (node (ref "C17") (pin "2") (pinfunction "2_2") (pintype "passive"))
      (node (ref "IC12") (pin "5") (pinfunction "+IN_5") (pintype "input"))
      (node (ref "R17") (pin "2") (pinfunction "2_2") (pintype "passive"))
    )
    (net (code "67") (name "Net-(IC12B--IN)") (class "Default")
      (node (ref "IC12") (pin "6") (pinfunction "-IN_6") (pintype "input"))
      (node (ref "IC12") (pin "7") (pinfunction "OUT_7") (pintype "output"))
      (node (ref "R10") (pin "2") (pinfunction "2_2") (pintype "passive"))
    )
    (net (code "68") (name "Net-(IC12C--IN)") (class "Default")
      (node (ref "IC12") (pin "9") (pinfunction "-IN_9") (pintype "input"))
      (node (ref "R10") (pin "1") (pinfunction "1_1") (pintype "passive"))
      (node (ref "R11") (pin "2") (pinfunction "2_2") (pintype "passive"))
    )
    (net (code "69") (name "Net-(IC12C-OUT)") (class "Default")
      (node (ref "IC12") (pin "8") (pinfunction "OUT_8") (pintype "output"))
      (node (ref "R11") (pin "1") (pinfunction "1_1") (pintype "passive"))
      (node (ref "R19") (pin "1") (pinfunction "1_1") (pintype "passive"))
    )
    (net (code "70") (name "Net-(U$1-3.3V2)") (class "Default")
      (node (ref "U$1") (pin "P$46") (pinfunction "3.3V2_P$46") (pintype "power_in"))
      (node (ref "U$2") (pin "1") (pinfunction "VDD_1") (pintype "power_in"))
    )
    (net (code "71") (name "unconnected-(IC1-DOUT-Pad10)") (class "Default")
      (node (ref "IC1") (pin "10") (pinfunction "DOUT_10") (pintype "output"))
    )
    (net (code "72") (name "unconnected-(IC5-NC_11-PadP$11)") (class "Default")
      (node (ref "IC5") (pin "P$11") (pinfunction "NC_11_P$11") (pintype "passive"))
    )
    (net (code "73") (name "unconnected-(IC5-NC_12-PadP$12)") (class "Default")
      (node (ref "IC5") (pin "P$12") (pinfunction "NC_12_P$12") (pintype "passive"))
    )
    (net (code "74") (name "unconnected-(IC5-NC_13-PadP$13)") (class "Default")
      (node (ref "IC5") (pin "P$13") (pinfunction "NC_13_P$13") (pintype "passive"))
    )
    (net (code "75") (name "unconnected-(IC5-NC_15-PadP$15)") (class "Default")
      (node (ref "IC5") (pin "P$15") (pinfunction "NC_15_P$15") (pintype "passive"))
    )
    (net (code "76") (name "unconnected-(IC5-NC_16-PadP$16)") (class "Default")
      (node (ref "IC5") (pin "P$16") (pinfunction "NC_16_P$16") (pintype "passive"))
    )
    (net (code "77") (name "unconnected-(IC5-NC_22-PadP$22)") (class "Default")
      (node (ref "IC5") (pin "P$22") (pinfunction "NC_22_P$22") (pintype "passive"))
    )
    (net (code "78") (name "unconnected-(IC5-NC_23-PadP$23)") (class "Default")
      (node (ref "IC5") (pin "P$23") (pinfunction "NC_23_P$23") (pintype "passive"))
    )
    (net (code "79") (name "unconnected-(IC8-N.C.-Pad15)") (class "Default")
      (node (ref "IC8") (pin "15") (pinfunction "N.C._15") (pintype "passive"))
    )
    (net (code "80") (name "unconnected-(IC8-NO2-Pad9)") (class "Default")
      (node (ref "IC8") (pin "9") (pinfunction "NO2_9") (pintype "passive"))
    )
    (net (code "81") (name "unconnected-(IC10-N.C.-Pad15)") (class "Default")
      (node (ref "IC10") (pin "15") (pinfunction "N.C._15") (pintype "passive"))
    )
    (net (code "82") (name "unconnected-(JP1-Pad3)") (class "Default")
      (node (ref "JP1") (pin "3") (pinfunction "3_3") (pintype "passive"))
    )
    (net (code "83") (name "unconnected-(JP2-Pad3)") (class "Default")
      (node (ref "JP2") (pin "3") (pinfunction "3_3") (pintype "passive"))
    )
  )
)
